# cell.net
KiCad netlist of a schematic drawn in EAGLE
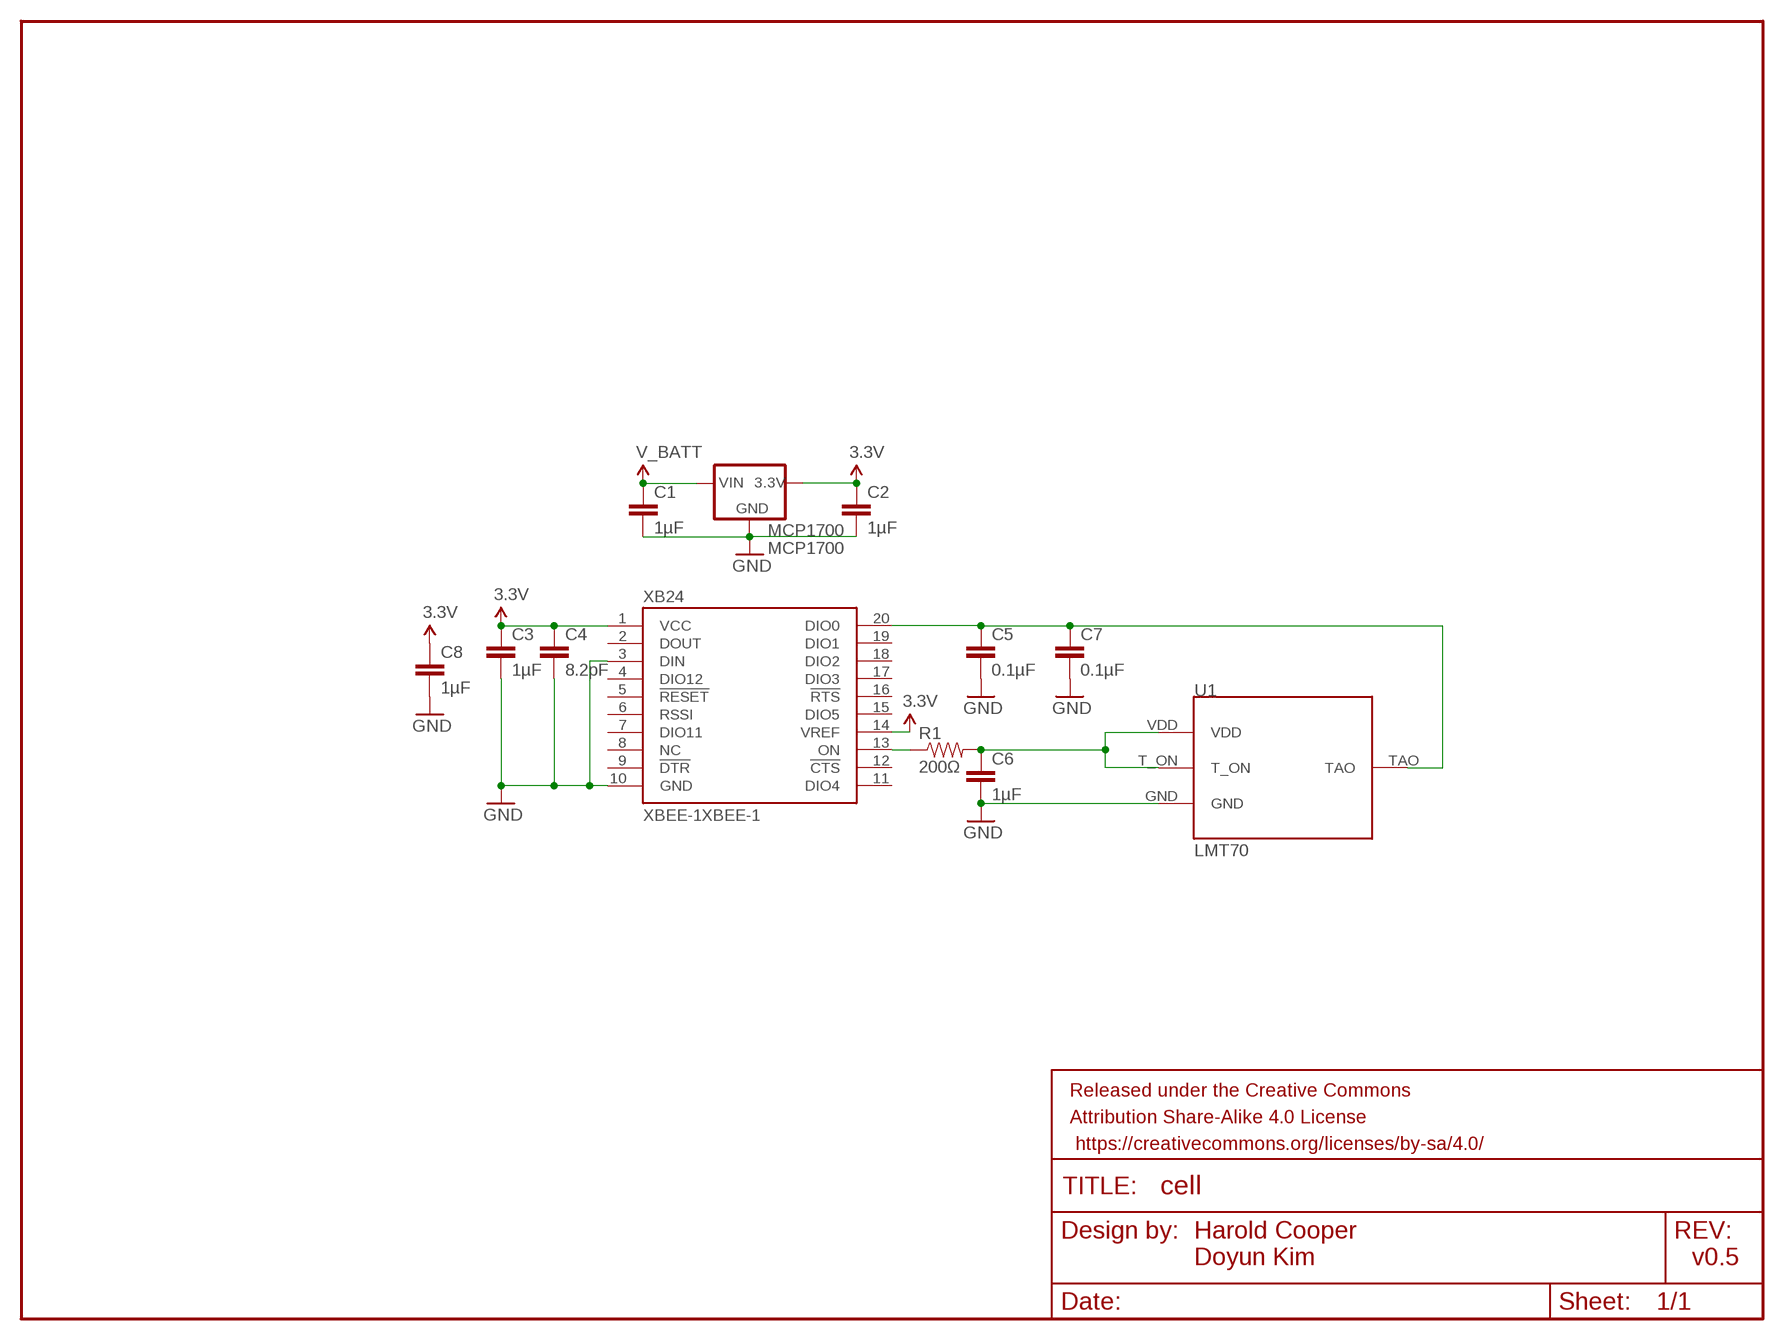
[diagram p0: schematic, sheet 1]

(export (version "E")
  (design (tool "Eeschema 10.0.6"))
  (components
    (comp (ref "C1")
      (value "1µF")
      (footprint "eagle-import:0805")
      (libsource (lib "eagle-import") (part "CAP0805"))
    )
    (comp (ref "C2")
      (value "1µF")
      (footprint "eagle-import:0805")
      (libsource (lib "eagle-import") (part "CAP0805"))
    )
    (comp (ref "C3")
      (value "1µF")
      (footprint "eagle-import:0805")
      (libsource (lib "eagle-import") (part "CAP0805"))
    )
    (comp (ref "C4")
      (value "8.2pF")
      (footprint "eagle-import:0805")
      (libsource (lib "eagle-import") (part "CAP0805"))
    )
    (comp (ref "C5")
      (value "0.1µF")
      (footprint "eagle-import:0805")
      (libsource (lib "eagle-import") (part "CAP0805"))
    )
    (comp (ref "C6")
      (value "1µF")
      (footprint "eagle-import:0805")
      (libsource (lib "eagle-import") (part "CAP0805"))
    )
    (comp (ref "C7")
      (value "0.1µF")
      (footprint "eagle-import:0805")
      (libsource (lib "eagle-import") (part "CAP0805"))
    )
    (comp (ref "C8")
      (value "1µF")
      (footprint "eagle-import:0805")
      (libsource (lib "eagle-import") (part "CAP0805"))
    )
    (comp (ref "FRAME1")
      (value "FRAME-LETTER")
      (footprint "eagle-import:CREATIVE_COMMONS")
      (libsource (lib "eagle-import") (part "FRAME-LETTER"))
    )
    (comp (ref "MCP1700")
      (value "MCP1700")
      (footprint "eagle-import:SOT-89-3")
      (libsource (lib "eagle-import") (part "MCP1700"))
    )
    (comp (ref "R1")
      (value "200Ω")
      (footprint "eagle-import:0805")
      (libsource (lib "eagle-import") (part "RESISTOR0805-RES"))
    )
    (comp (ref "U1")
      (value "LMT70")
      (footprint "eagle-import:YFP0004")
      (libsource (lib "eagle-import") (part "LMT70"))
    )
    (comp (ref "XB24")
      (value "XBEE-1XBEE-1")
      (footprint "eagle-import:XBEE-1")
      (libsource (lib "eagle-import") (part "XBEE-1XBEE-1"))
    )
  )
  (nets
    (net (code "1") (name "3.3V") (class "Default")
      (node (ref "C2") (pin "1") (pinfunction "1_1") (pintype "passive"))
      (node (ref "C3") (pin "1") (pinfunction "1_1") (pintype "passive"))
      (node (ref "C4") (pin "1") (pinfunction "1_1") (pintype "passive"))
      (node (ref "C8") (pin "1") (pinfunction "1_1") (pintype "passive"))
      (node (ref "MCP1700") (pin "3") (pinfunction "3.3V_3") (pintype "output"))
      (node (ref "XB24") (pin "1") (pinfunction "VCC_1") (pintype "power_in"))
      (node (ref "XB24") (pin "14") (pinfunction "VREF_14") (pintype "power_in"))
    )
    (net (code "2") (name "GND") (class "Default")
      (node (ref "C1") (pin "2") (pinfunction "2_2") (pintype "passive"))
      (node (ref "C2") (pin "2") (pinfunction "2_2") (pintype "passive"))
      (node (ref "C3") (pin "2") (pinfunction "2_2") (pintype "passive"))
      (node (ref "C4") (pin "2") (pinfunction "2_2") (pintype "passive"))
      (node (ref "C5") (pin "2") (pinfunction "2_2") (pintype "passive"))
      (node (ref "C6") (pin "2") (pinfunction "2_2") (pintype "passive"))
      (node (ref "C7") (pin "2") (pinfunction "2_2") (pintype "passive"))
      (node (ref "C8") (pin "2") (pinfunction "2_2") (pintype "passive"))
      (node (ref "MCP1700") (pin "1") (pinfunction "GND_1") (pintype "power_in"))
      (node (ref "U1") (pin "GND") (pinfunction "GND_GND") (pintype "input"))
      (node (ref "XB24") (pin "10") (pinfunction "GND_10") (pintype "power_in"))
      (node (ref "XB24") (pin "3") (pinfunction "DIN_3") (pintype "input"))
    )
    (net (code "3") (name "Net-(C6-Pad1)") (class "Default")
      (node (ref "C6") (pin "1") (pinfunction "1_1") (pintype "passive"))
      (node (ref "R1") (pin "2") (pinfunction "2_2") (pintype "passive"))
      (node (ref "U1") (pin "T_ON") (pinfunction "T_ON_T_ON") (pintype "input"))
      (node (ref "U1") (pin "VDD") (pinfunction "VDD_VDD") (pintype "input"))
    )
    (net (code "4") (name "Net-(XB24-DIO0)") (class "Default")
      (node (ref "C5") (pin "1") (pinfunction "1_1") (pintype "passive"))
      (node (ref "C7") (pin "1") (pinfunction "1_1") (pintype "passive"))
      (node (ref "U1") (pin "TAO") (pinfunction "TAO_TAO") (pintype "output"))
      (node (ref "XB24") (pin "20") (pinfunction "DIO0_20") (pintype "bidirectional"))
    )
    (net (code "5") (name "Net-(XB24-ON)") (class "Default")
      (node (ref "R1") (pin "1") (pinfunction "1_1") (pintype "passive"))
      (node (ref "XB24") (pin "13") (pinfunction "ON_13") (pintype "bidirectional"))
    )
    (net (code "6") (name "V_BATT") (class "Default")
      (node (ref "C1") (pin "1") (pinfunction "1_1") (pintype "passive"))
      (node (ref "MCP1700") (pin "2") (pinfunction "IN_2") (pintype "power_in"))
    )
    (net (code "7") (name "unconnected-(XB24-DIO1-Pad19)") (class "Default")
      (node (ref "XB24") (pin "19") (pinfunction "DIO1_19") (pintype "bidirectional"))
    )
    (net (code "8") (name "unconnected-(XB24-DIO2-Pad18)") (class "Default")
      (node (ref "XB24") (pin "18") (pinfunction "DIO2_18") (pintype "bidirectional"))
    )
    (net (code "9") (name "unconnected-(XB24-DIO3-Pad17)") (class "Default")
      (node (ref "XB24") (pin "17") (pinfunction "DIO3_17") (pintype "bidirectional"))
    )
    (net (code "10") (name "unconnected-(XB24-DIO4-Pad11)") (class "Default")
      (node (ref "XB24") (pin "11") (pinfunction "DIO4_11") (pintype "bidirectional"))
    )
    (net (code "11") (name "unconnected-(XB24-DIO5-Pad15)") (class "Default")
      (node (ref "XB24") (pin "15") (pinfunction "DIO5_15") (pintype "bidirectional"))
    )
    (net (code "12") (name "unconnected-(XB24-DIO11-Pad7)") (class "Default")
      (node (ref "XB24") (pin "7") (pinfunction "DIO11_7") (pintype "bidirectional"))
    )
    (net (code "13") (name "unconnected-(XB24-DIO12-Pad4)") (class "Default")
      (node (ref "XB24") (pin "4") (pinfunction "DIO12_4") (pintype "bidirectional"))
    )
    (net (code "14") (name "unconnected-(XB24-DOUT-Pad2)") (class "Default")
      (node (ref "XB24") (pin "2") (pinfunction "DOUT_2") (pintype "output"))
    )
    (net (code "15") (name "unconnected-(XB24-NC-Pad8)") (class "Default")
      (node (ref "XB24") (pin "8") (pinfunction "NC_8") (pintype "no_connect"))
    )
    (net (code "16") (name "unconnected-(XB24-RSSI-Pad6)") (class "Default")
      (node (ref "XB24") (pin "6") (pinfunction "RSSI_6") (pintype "bidirectional"))
    )
    (net (code "17") (name "unconnected-(XB24-~{CTS}-Pad12)") (class "Default")
      (node (ref "XB24") (pin "12") (pinfunction "~{CTS}_12") (pintype "output"))
    )
    (net (code "18") (name "unconnected-(XB24-~{DTR}-Pad9)") (class "Default")
      (node (ref "XB24") (pin "9") (pinfunction "~{DTR}_9") (pintype "bidirectional"))
    )
    (net (code "19") (name "unconnected-(XB24-~{RESET}-Pad5)") (class "Default")
      (node (ref "XB24") (pin "5") (pinfunction "~{RESET}_5") (pintype "input"))
    )
    (net (code "20") (name "unconnected-(XB24-~{RTS}-Pad16)") (class "Default")
      (node (ref "XB24") (pin "16") (pinfunction "~{RTS}_16") (pintype "input"))
    )
  )
)
